# estop_tx.net
KiCad netlist of a schematic drawn in EAGLE
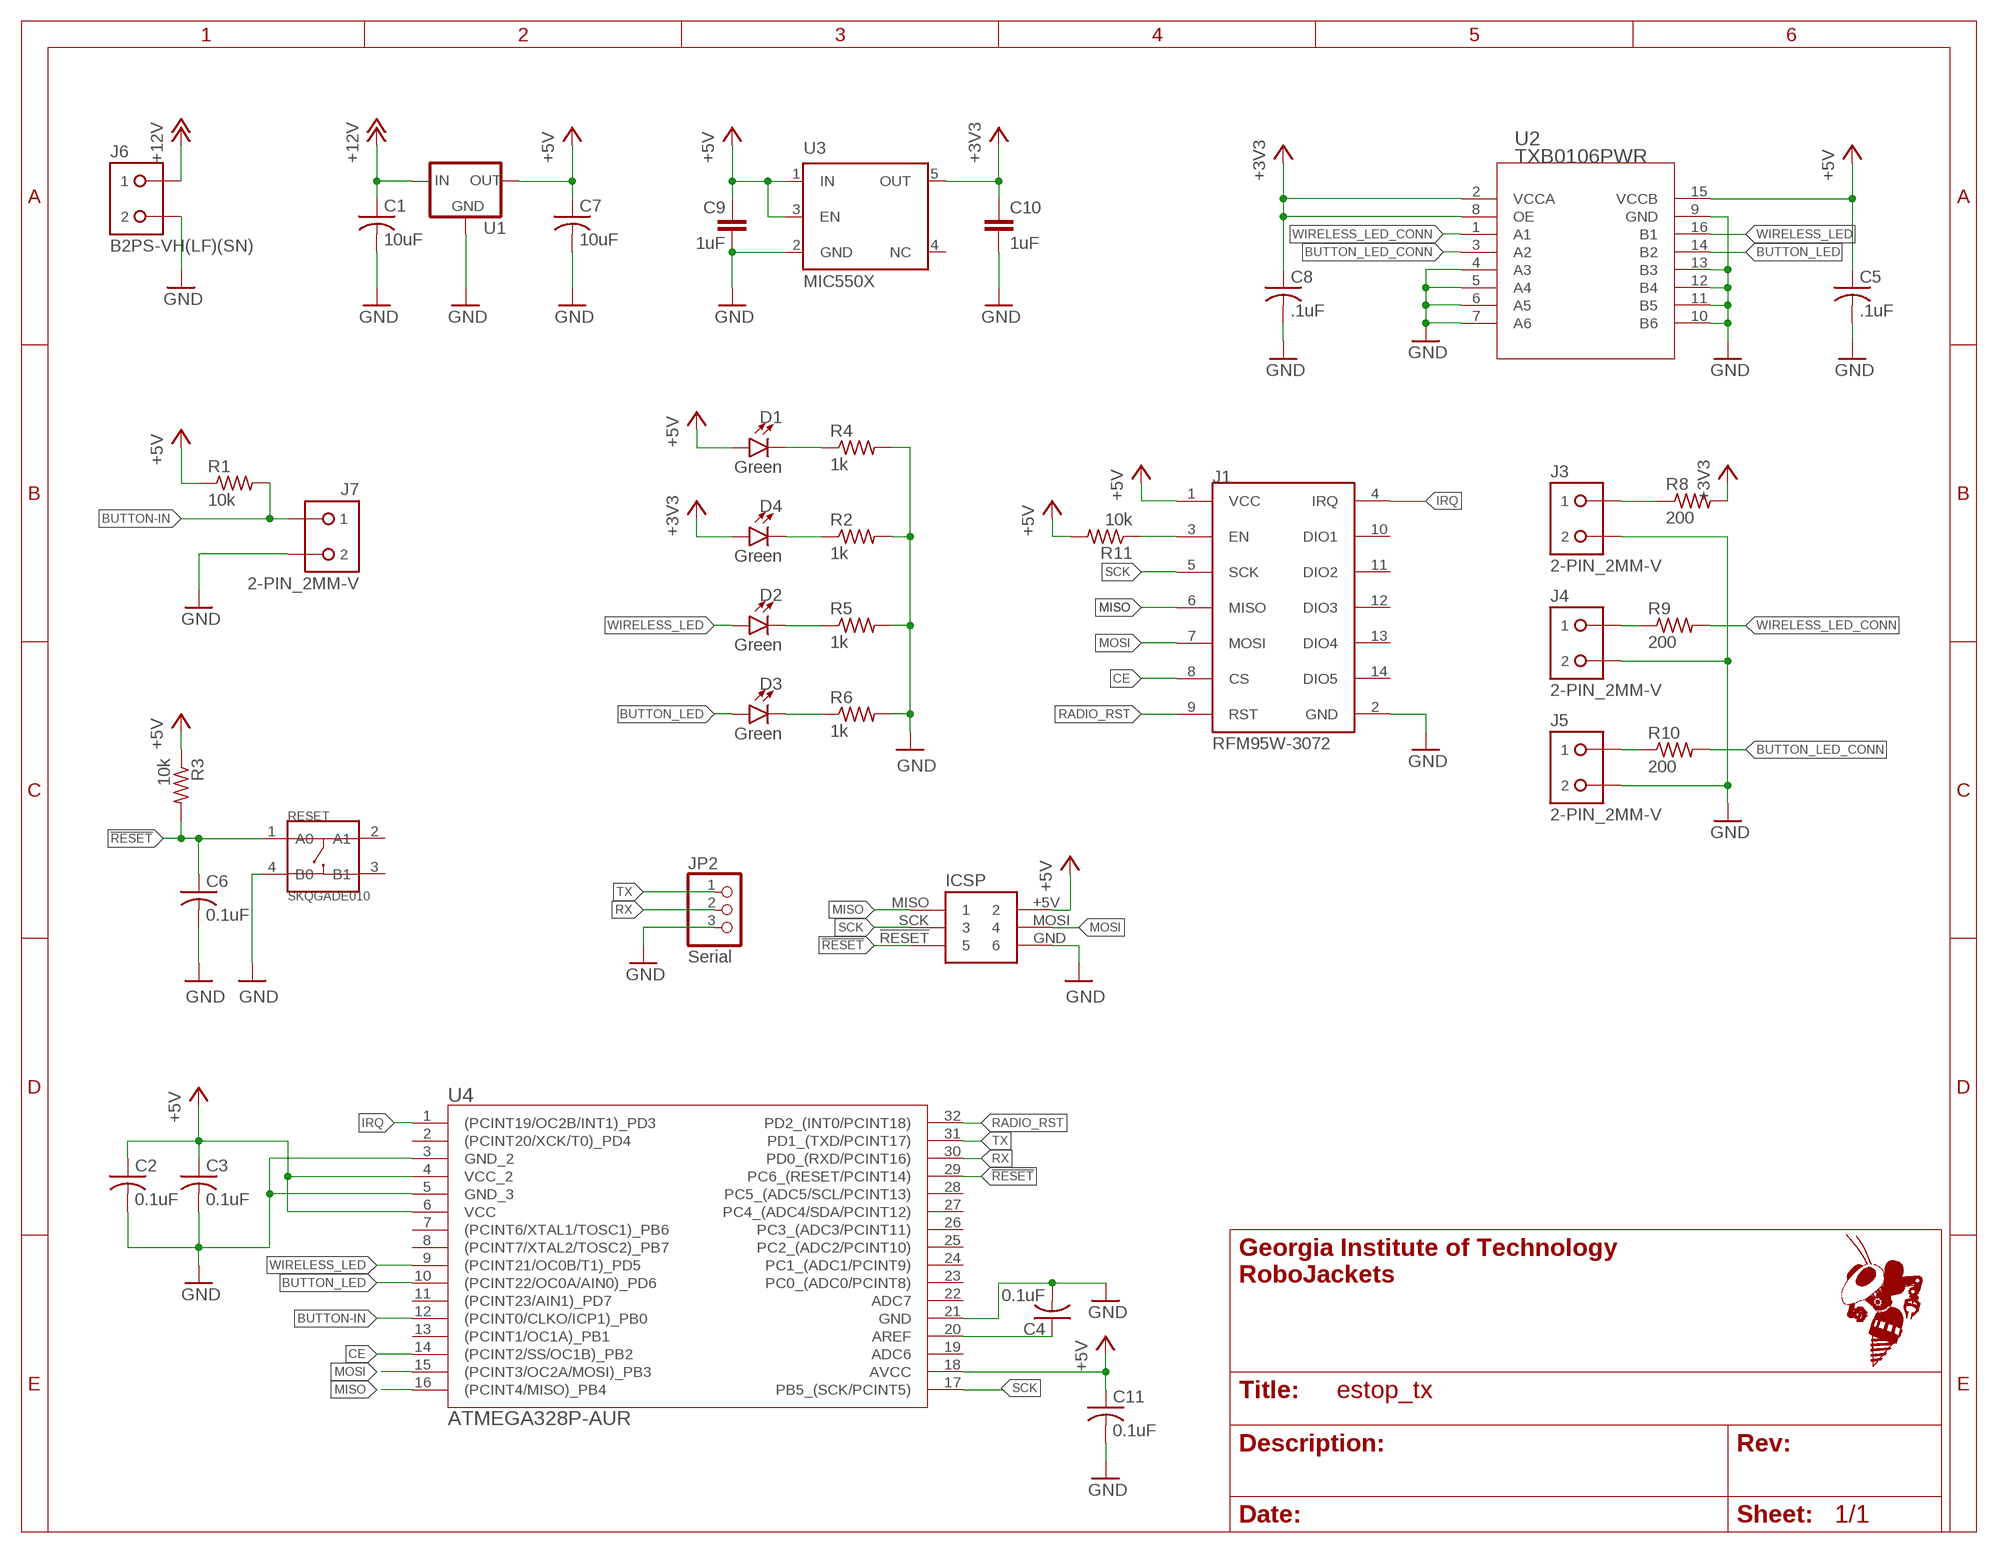
[diagram p0: schematic, sheet 1]

(export (version "E")
  (design (tool "Eeschema 10.0.6"))
  (components
    (comp (ref "C1")
      (value "10uF")
      (footprint "eagle-import:C0805")
      (libsource (lib "eagle-import") (part "C-USC0805"))
    )
    (comp (ref "C2")
      (value "0.1uF")
      (footprint "eagle-import:C0603")
      (libsource (lib "eagle-import") (part "C-USC0603"))
    )
    (comp (ref "C3")
      (value "0.1uF")
      (footprint "eagle-import:C0603")
      (libsource (lib "eagle-import") (part "C-USC0603"))
    )
    (comp (ref "C4")
      (value "0.1uF")
      (footprint "eagle-import:C0603")
      (libsource (lib "eagle-import") (part "C-USC0603"))
    )
    (comp (ref "C5")
      (value ".1uF")
      (footprint "eagle-import:C0603")
      (libsource (lib "eagle-import") (part "C-USC0603"))
    )
    (comp (ref "C6")
      (value "0.1uF")
      (footprint "eagle-import:C0603")
      (libsource (lib "eagle-import") (part "C-USC0603"))
    )
    (comp (ref "C7")
      (value "10uF")
      (footprint "eagle-import:C0805")
      (libsource (lib "eagle-import") (part "C-USC0805"))
    )
    (comp (ref "C8")
      (value ".1uF")
      (footprint "eagle-import:C0603")
      (libsource (lib "eagle-import") (part "C-USC0603"))
    )
    (comp (ref "C9")
      (value "1uF")
      (footprint "eagle-import:C0603")
      (libsource (lib "eagle-import") (part "C-EUC0603"))
    )
    (comp (ref "C10")
      (value "1uF")
      (footprint "eagle-import:C0603")
      (libsource (lib "eagle-import") (part "C-EUC0603"))
    )
    (comp (ref "C11")
      (value "0.1uF")
      (footprint "eagle-import:C0603")
      (libsource (lib "eagle-import") (part "C-USC0603"))
    )
    (comp (ref "D1")
      (value "Green")
      (footprint "eagle-import:LED-0603")
      (libsource (lib "eagle-import") (part "LED-YELLOW0603"))
    )
    (comp (ref "D2")
      (value "Green")
      (footprint "eagle-import:LED-0603")
      (libsource (lib "eagle-import") (part "LED-YELLOW0603"))
    )
    (comp (ref "D3")
      (value "Green")
      (footprint "eagle-import:LED-0603")
      (libsource (lib "eagle-import") (part "LED-YELLOW0603"))
    )
    (comp (ref "D4")
      (value "Green")
      (footprint "eagle-import:LED-0603")
      (libsource (lib "eagle-import") (part "LED-YELLOW0603"))
    )
    (comp (ref "ICSP")
      (value "ICSP Connector")
      (footprint "eagle-import:2X3SHROUDED")
      (libsource (lib "eagle-import") (part "2X3SHROUDED"))
    )
    (comp (ref "J1")
      (value "RFM95W-3072")
      (footprint "eagle-import:RFM95W-3072")
      (libsource (lib "eagle-import") (part "RFM95W-3072"))
    )
    (comp (ref "J3")
      (value "2-PIN_2MM-V")
      (footprint "eagle-import:2MM-2-V")
      (libsource (lib "eagle-import") (part "2-PIN_2MM-V"))
    )
    (comp (ref "J4")
      (value "2-PIN_2MM-V")
      (footprint "eagle-import:2MM-2-V")
      (libsource (lib "eagle-import") (part "2-PIN_2MM-V"))
    )
    (comp (ref "J5")
      (value "2-PIN_2MM-V")
      (footprint "eagle-import:2MM-2-V")
      (libsource (lib "eagle-import") (part "2-PIN_2MM-V"))
    )
    (comp (ref "J6")
      (value "B2PS-VH(LF)(SN)")
      (footprint "eagle-import:B2PS-CENTERED")
      (libsource (lib "eagle-import") (part "B2P?-VH(LF)(SN)S"))
    )
    (comp (ref "J7")
      (value "2-PIN_2MM-V")
      (footprint "eagle-import:2MM-2-V")
      (libsource (lib "eagle-import") (part "2-PIN_2MM-V"))
    )
    (comp (ref "JP2")
      (value "Serial")
      (footprint "eagle-import:1X03")
      (libsource (lib "eagle-import") (part "PINHD-1X3"))
    )
    (comp (ref "R1")
      (value "10k")
      (footprint "eagle-import:R0603")
      (libsource (lib "eagle-import") (part "resistor_348_R-US_R0603"))
    )
    (comp (ref "R2")
      (value "1k")
      (footprint "eagle-import:R0603")
      (libsource (lib "eagle-import") (part "R-US_R0603"))
    )
    (comp (ref "R3")
      (value "10k")
      (footprint "eagle-import:R0603")
      (libsource (lib "eagle-import") (part "R-US_R0603"))
    )
    (comp (ref "R4")
      (value "1k")
      (footprint "eagle-import:R0603")
      (libsource (lib "eagle-import") (part "R-US_R0603"))
    )
    (comp (ref "R5")
      (value "1k")
      (footprint "eagle-import:R0603")
      (libsource (lib "eagle-import") (part "R-US_R0603"))
    )
    (comp (ref "R6")
      (value "1k")
      (footprint "eagle-import:R0603")
      (libsource (lib "eagle-import") (part "R-US_R0603"))
    )
    (comp (ref "R8")
      (value "200")
      (footprint "eagle-import:R0603")
      (libsource (lib "eagle-import") (part "R-US_R0603"))
    )
    (comp (ref "R9")
      (value "200")
      (footprint "eagle-import:R0603")
      (libsource (lib "eagle-import") (part "R-US_R0603"))
    )
    (comp (ref "R10")
      (value "200")
      (footprint "eagle-import:R0603")
      (libsource (lib "eagle-import") (part "R-US_R0603"))
    )
    (comp (ref "R11")
      (value "10k")
      (footprint "eagle-import:R0603")
      (libsource (lib "eagle-import") (part "R-US_R0603"))
    )
    (comp (ref "RESET")
      (value "SKQGADE010")
      (footprint "eagle-import:SW4-SMD-5.2X5.2X1.5MM")
      (libsource (lib "eagle-import") (part "SMD-SWITCH-TOP-260GF(4P-D5.2MM)"))
    )
    (comp (ref "U1")
      (value "R-78E5.0-1.0CONV_R-78E5.0-1.0")
      (footprint "eagle-import:CONV_R-78E5.0-1.0")
      (libsource (lib "eagle-import") (part "R-78E5.0-1.0CONV_R-78E5.0-1.0"))
    )
    (comp (ref "U2")
      (value "TXB0106PWR")
      (footprint "eagle-import:PW16")
      (libsource (lib "eagle-import") (part "TXB0106PWR"))
    )
    (comp (ref "U3")
      (value "MIC550X")
      (footprint "eagle-import:SOT23-DBV")
      (libsource (lib "eagle-import") (part "MIC550X"))
    )
    (comp (ref "U4")
      (value "ATMEGA328P-AUR")
      (footprint "eagle-import:ATMEGA328P-AUR")
      (libsource (lib "eagle-import") (part "ATMEGA328P-AUR"))
    )
  )
  (nets
    (net (code "1") (name "+3V3") (class "Default")
      (node (ref "C10") (pin "1") (pinfunction "1_1") (pintype "passive"))
      (node (ref "C8") (pin "1") (pinfunction "1_1") (pintype "passive"))
      (node (ref "D4") (pin "A") (pinfunction "A_A") (pintype "passive"))
      (node (ref "R8") (pin "2") (pinfunction "2_2") (pintype "passive"))
      (node (ref "U2") (pin "2") (pinfunction "VCCA_2") (pintype "power_in"))
      (node (ref "U2") (pin "8") (pinfunction "OE_8") (pintype "output"))
      (node (ref "U3") (pin "5") (pinfunction "OUT_5") (pintype "passive"))
    )
    (net (code "2") (name "+5V") (class "Default")
      (node (ref "C11") (pin "1") (pinfunction "1_1") (pintype "passive"))
      (node (ref "C2") (pin "1") (pinfunction "1_1") (pintype "passive"))
      (node (ref "C3") (pin "1") (pinfunction "1_1") (pintype "passive"))
      (node (ref "C5") (pin "1") (pinfunction "1_1") (pintype "passive"))
      (node (ref "C7") (pin "1") (pinfunction "1_1") (pintype "passive"))
      (node (ref "C9") (pin "1") (pinfunction "1_1") (pintype "passive"))
      (node (ref "D1") (pin "A") (pinfunction "A_A") (pintype "passive"))
      (node (ref "ICSP") (pin "+5V") (pinfunction "2_+5V") (pintype "bidirectional"))
      (node (ref "J1") (pin "1") (pinfunction "VCC_1") (pintype "passive"))
      (node (ref "R1") (pin "1") (pinfunction "1_1") (pintype "passive"))
      (node (ref "R11") (pin "2") (pinfunction "2_2") (pintype "passive"))
      (node (ref "R3") (pin "1") (pinfunction "1_1") (pintype "passive"))
      (node (ref "U1") (pin "3") (pinfunction "OUT_3") (pintype "passive"))
      (node (ref "U2") (pin "15") (pinfunction "VCCB_15") (pintype "power_in"))
      (node (ref "U3") (pin "1") (pinfunction "IN_1") (pintype "input"))
      (node (ref "U3") (pin "3") (pinfunction "EN_3") (pintype "input"))
      (node (ref "U4") (pin "18") (pinfunction "AVCC_18") (pintype "bidirectional"))
      (node (ref "U4") (pin "4") (pinfunction "VCC_2_4") (pintype "bidirectional"))
      (node (ref "U4") (pin "6") (pinfunction "VCC_6") (pintype "bidirectional"))
    )
    (net (code "3") (name "+12V") (class "Default")
      (node (ref "C1") (pin "1") (pinfunction "1_1") (pintype "passive"))
      (node (ref "J6") (pin "1") (pinfunction "1_1") (pintype "bidirectional"))
      (node (ref "U1") (pin "1") (pinfunction "IN_1") (pintype "input"))
    )
    (net (code "4") (name "/~{RESET}") (class "Default")
      (node (ref "C6") (pin "1") (pinfunction "1_1") (pintype "passive"))
      (node (ref "ICSP") (pin "!RESET") (pinfunction "5_!RESET") (pintype "bidirectional"))
      (node (ref "R3") (pin "2") (pinfunction "2_2") (pintype "passive"))
      (node (ref "RESET") (pin "1") (pinfunction "A0_1") (pintype "bidirectional"))
      (node (ref "U4") (pin "29") (pinfunction "PC6_(RESET/PCINT14)_29") (pintype "bidirectional"))
    )
    (net (code "5") (name "BUTTON-IN") (class "Default")
      (node (ref "J7") (pin "1") (pinfunction "1_1") (pintype "bidirectional"))
      (node (ref "R1") (pin "2") (pinfunction "2_2") (pintype "passive"))
      (node (ref "U4") (pin "12") (pinfunction "(PCINT0/CLKO/ICP1)_PB0_12") (pintype "bidirectional"))
    )
    (net (code "6") (name "BUTTON_LED") (class "Default")
      (node (ref "D3") (pin "A") (pinfunction "A_A") (pintype "passive"))
      (node (ref "U2") (pin "14") (pinfunction "B2_14") (pintype "bidirectional"))
      (node (ref "U4") (pin "10") (pinfunction "(PCINT22/OC0A/AIN0)_PD6_10") (pintype "bidirectional"))
    )
    (net (code "7") (name "BUTTON_LED_CONN") (class "Default")
      (node (ref "R10") (pin "2") (pinfunction "2_2") (pintype "passive"))
      (node (ref "U2") (pin "3") (pinfunction "A2_3") (pintype "bidirectional"))
    )
    (net (code "8") (name "CE") (class "Default")
      (node (ref "J1") (pin "8") (pinfunction "CS_8") (pintype "passive"))
      (node (ref "U4") (pin "14") (pinfunction "(PCINT2/SS/OC1B)_PB2_14") (pintype "bidirectional"))
    )
    (net (code "9") (name "GND") (class "Default")
      (node (ref "C1") (pin "2") (pinfunction "2_2") (pintype "passive"))
      (node (ref "C10") (pin "2") (pinfunction "2_2") (pintype "passive"))
      (node (ref "C11") (pin "2") (pinfunction "2_2") (pintype "passive"))
      (node (ref "C2") (pin "2") (pinfunction "2_2") (pintype "passive"))
      (node (ref "C3") (pin "2") (pinfunction "2_2") (pintype "passive"))
      (node (ref "C4") (pin "2") (pinfunction "2_2") (pintype "passive"))
      (node (ref "C5") (pin "2") (pinfunction "2_2") (pintype "passive"))
      (node (ref "C6") (pin "2") (pinfunction "2_2") (pintype "passive"))
      (node (ref "C7") (pin "2") (pinfunction "2_2") (pintype "passive"))
      (node (ref "C8") (pin "2") (pinfunction "2_2") (pintype "passive"))
      (node (ref "C9") (pin "2") (pinfunction "2_2") (pintype "passive"))
      (node (ref "ICSP") (pin "GND") (pinfunction "6_GND") (pintype "bidirectional"))
      (node (ref "J1") (pin "2") (pinfunction "GND_2") (pintype "passive"))
      (node (ref "J3") (pin "2") (pinfunction "2_2") (pintype "bidirectional"))
      (node (ref "J4") (pin "2") (pinfunction "2_2") (pintype "bidirectional"))
      (node (ref "J5") (pin "2") (pinfunction "2_2") (pintype "bidirectional"))
      (node (ref "J6") (pin "2") (pinfunction "2_2") (pintype "bidirectional"))
      (node (ref "J7") (pin "2") (pinfunction "2_2") (pintype "bidirectional"))
      (node (ref "JP2") (pin "3") (pinfunction "3_3") (pintype "passive"))
      (node (ref "R2") (pin "2") (pinfunction "2_2") (pintype "passive"))
      (node (ref "R4") (pin "2") (pinfunction "2_2") (pintype "passive"))
      (node (ref "R5") (pin "2") (pinfunction "2_2") (pintype "passive"))
      (node (ref "R6") (pin "2") (pinfunction "2_2") (pintype "passive"))
      (node (ref "RESET") (pin "4") (pinfunction "B0_4") (pintype "bidirectional"))
      (node (ref "U1") (pin "2") (pinfunction "GND_2") (pintype "input"))
      (node (ref "U2") (pin "10") (pinfunction "B6_10") (pintype "bidirectional"))
      (node (ref "U2") (pin "11") (pinfunction "B5_11") (pintype "bidirectional"))
      (node (ref "U2") (pin "12") (pinfunction "B4_12") (pintype "bidirectional"))
      (node (ref "U2") (pin "13") (pinfunction "B3_13") (pintype "bidirectional"))
      (node (ref "U2") (pin "4") (pinfunction "A3_4") (pintype "bidirectional"))
      (node (ref "U2") (pin "5") (pinfunction "A4_5") (pintype "bidirectional"))
      (node (ref "U2") (pin "6") (pinfunction "A5_6") (pintype "bidirectional"))
      (node (ref "U2") (pin "7") (pinfunction "A6_7") (pintype "bidirectional"))
      (node (ref "U2") (pin "9") (pinfunction "GND_9") (pintype "power_in"))
      (node (ref "U3") (pin "2") (pinfunction "GND_2") (pintype "output"))
      (node (ref "U4") (pin "21") (pinfunction "GND_21") (pintype "bidirectional"))
      (node (ref "U4") (pin "3") (pinfunction "GND_2_3") (pintype "bidirectional"))
      (node (ref "U4") (pin "5") (pinfunction "GND_3_5") (pintype "bidirectional"))
    )
    (net (code "10") (name "IRQ") (class "Default")
      (node (ref "J1") (pin "4") (pinfunction "IRQ_4") (pintype "passive"))
      (node (ref "U4") (pin "1") (pinfunction "(PCINT19/OC2B/INT1)_PD3_1") (pintype "bidirectional"))
    )
    (net (code "11") (name "MISO") (class "Default")
      (node (ref "ICSP") (pin "MISO") (pinfunction "1_MISO") (pintype "bidirectional"))
      (node (ref "J1") (pin "6") (pinfunction "MISO_6") (pintype "passive"))
      (node (ref "U4") (pin "16") (pinfunction "(PCINT4/MISO)_PB4_16") (pintype "bidirectional"))
    )
    (net (code "12") (name "MOSI") (class "Default")
      (node (ref "ICSP") (pin "MOSI") (pinfunction "4_MOSI") (pintype "bidirectional"))
      (node (ref "J1") (pin "7") (pinfunction "MOSI_7") (pintype "passive"))
      (node (ref "U4") (pin "15") (pinfunction "(PCINT3/OC2A/MOSI)_PB3_15") (pintype "bidirectional"))
    )
    (net (code "13") (name "Net-(D1-PadC)") (class "Default")
      (node (ref "D1") (pin "C") (pinfunction "C_C") (pintype "passive"))
      (node (ref "R4") (pin "1") (pinfunction "1_1") (pintype "passive"))
    )
    (net (code "14") (name "Net-(D2-PadC)") (class "Default")
      (node (ref "D2") (pin "C") (pinfunction "C_C") (pintype "passive"))
      (node (ref "R5") (pin "1") (pinfunction "1_1") (pintype "passive"))
    )
    (net (code "15") (name "Net-(D3-PadC)") (class "Default")
      (node (ref "D3") (pin "C") (pinfunction "C_C") (pintype "passive"))
      (node (ref "R6") (pin "1") (pinfunction "1_1") (pintype "passive"))
    )
    (net (code "16") (name "Net-(D4-PadC)") (class "Default")
      (node (ref "D4") (pin "C") (pinfunction "C_C") (pintype "passive"))
      (node (ref "R2") (pin "1") (pinfunction "1_1") (pintype "passive"))
    )
    (net (code "17") (name "Net-(J1-EN)") (class "Default")
      (node (ref "J1") (pin "3") (pinfunction "EN_3") (pintype "passive"))
      (node (ref "R11") (pin "1") (pinfunction "1_1") (pintype "passive"))
    )
    (net (code "18") (name "Net-(J3-Pad1)") (class "Default")
      (node (ref "J3") (pin "1") (pinfunction "1_1") (pintype "bidirectional"))
      (node (ref "R8") (pin "1") (pinfunction "1_1") (pintype "passive"))
    )
    (net (code "19") (name "Net-(J4-Pad1)") (class "Default")
      (node (ref "J4") (pin "1") (pinfunction "1_1") (pintype "bidirectional"))
      (node (ref "R9") (pin "1") (pinfunction "1_1") (pintype "passive"))
    )
    (net (code "20") (name "Net-(J5-Pad1)") (class "Default")
      (node (ref "J5") (pin "1") (pinfunction "1_1") (pintype "bidirectional"))
      (node (ref "R10") (pin "1") (pinfunction "1_1") (pintype "passive"))
    )
    (net (code "21") (name "Net-(U4-AREF)") (class "Default")
      (node (ref "C4") (pin "1") (pinfunction "1_1") (pintype "passive"))
      (node (ref "U4") (pin "20") (pinfunction "AREF_20") (pintype "bidirectional"))
    )
    (net (code "22") (name "RADIO_RST") (class "Default")
      (node (ref "J1") (pin "9") (pinfunction "RST_9") (pintype "passive"))
      (node (ref "U4") (pin "32") (pinfunction "PD2_(INT0/PCINT18)_32") (pintype "bidirectional"))
    )
    (net (code "23") (name "RX") (class "Default")
      (node (ref "JP2") (pin "2") (pinfunction "2_2") (pintype "passive"))
      (node (ref "U4") (pin "30") (pinfunction "PD0_(RXD/PCINT16)_30") (pintype "bidirectional"))
    )
    (net (code "24") (name "SCK") (class "Default")
      (node (ref "ICSP") (pin "SCK") (pinfunction "3_SCK") (pintype "bidirectional"))
      (node (ref "J1") (pin "5") (pinfunction "SCK_5") (pintype "passive"))
      (node (ref "U4") (pin "17") (pinfunction "PB5_(SCK/PCINT5)_17") (pintype "bidirectional"))
    )
    (net (code "25") (name "TX") (class "Default")
      (node (ref "JP2") (pin "1") (pinfunction "1_1") (pintype "passive"))
      (node (ref "U4") (pin "31") (pinfunction "PD1_(TXD/PCINT17)_31") (pintype "bidirectional"))
    )
    (net (code "26") (name "WIRELESS_LED") (class "Default")
      (node (ref "D2") (pin "A") (pinfunction "A_A") (pintype "passive"))
      (node (ref "U2") (pin "16") (pinfunction "B1_16") (pintype "bidirectional"))
      (node (ref "U4") (pin "9") (pinfunction "(PCINT21/OC0B/T1)_PD5_9") (pintype "bidirectional"))
    )
    (net (code "27") (name "WIRELESS_LED_CONN") (class "Default")
      (node (ref "R9") (pin "2") (pinfunction "2_2") (pintype "passive"))
      (node (ref "U2") (pin "1") (pinfunction "A1_1") (pintype "bidirectional"))
    )
    (net (code "28") (name "unconnected-(J1-DIO1-Pad10)") (class "Default")
      (node (ref "J1") (pin "10") (pinfunction "DIO1_10") (pintype "bidirectional"))
    )
    (net (code "29") (name "unconnected-(J1-DIO2-Pad11)") (class "Default")
      (node (ref "J1") (pin "11") (pinfunction "DIO2_11") (pintype "bidirectional"))
    )
    (net (code "30") (name "unconnected-(J1-DIO3-Pad12)") (class "Default")
      (node (ref "J1") (pin "12") (pinfunction "DIO3_12") (pintype "bidirectional"))
    )
    (net (code "31") (name "unconnected-(J1-DIO4-Pad13)") (class "Default")
      (node (ref "J1") (pin "13") (pinfunction "DIO4_13") (pintype "bidirectional"))
    )
    (net (code "32") (name "unconnected-(J1-DIO5-Pad14)") (class "Default")
      (node (ref "J1") (pin "14") (pinfunction "DIO5_14") (pintype "bidirectional"))
    )
    (net (code "33") (name "unconnected-(RESET-A1-Pad2)") (class "Default")
      (node (ref "RESET") (pin "2") (pinfunction "A1_2") (pintype "bidirectional"))
    )
    (net (code "34") (name "unconnected-(RESET-B1-Pad3)") (class "Default")
      (node (ref "RESET") (pin "3") (pinfunction "B1_3") (pintype "bidirectional"))
    )
    (net (code "35") (name "unconnected-(U3-NC-Pad4)") (class "Default")
      (node (ref "U3") (pin "4") (pinfunction "NC_4") (pintype "tri_state"))
    )
    (net (code "36") (name "unconnected-(U4-(PCINT1{slash}OC1A)_PB1-Pad13)") (class "Default")
      (node (ref "U4") (pin "13") (pinfunction "(PCINT1/OC1A)_PB1_13") (pintype "bidirectional"))
    )
    (net (code "37") (name "unconnected-(U4-(PCINT6{slash}XTAL1{slash}TOSC1)_PB6-Pad7)") (class "Default")
      (node (ref "U4") (pin "7") (pinfunction "(PCINT6/XTAL1/TOSC1)_PB6_7") (pintype "bidirectional"))
    )
    (net (code "38") (name "unconnected-(U4-(PCINT7{slash}XTAL2{slash}TOSC2)_PB7-Pad8)") (class "Default")
      (node (ref "U4") (pin "8") (pinfunction "(PCINT7/XTAL2/TOSC2)_PB7_8") (pintype "bidirectional"))
    )
    (net (code "39") (name "unconnected-(U4-(PCINT20{slash}XCK{slash}T0)_PD4-Pad2)") (class "Default")
      (node (ref "U4") (pin "2") (pinfunction "(PCINT20/XCK/T0)_PD4_2") (pintype "bidirectional"))
    )
    (net (code "40") (name "unconnected-(U4-(PCINT23{slash}AIN1)_PD7-Pad11)") (class "Default")
      (node (ref "U4") (pin "11") (pinfunction "(PCINT23/AIN1)_PD7_11") (pintype "bidirectional"))
    )
    (net (code "41") (name "unconnected-(U4-ADC6-Pad19)") (class "Default")
      (node (ref "U4") (pin "19") (pinfunction "ADC6_19") (pintype "bidirectional"))
    )
    (net (code "42") (name "unconnected-(U4-ADC7-Pad22)") (class "Default")
      (node (ref "U4") (pin "22") (pinfunction "ADC7_22") (pintype "bidirectional"))
    )
    (net (code "43") (name "unconnected-(U4-PC0_(ADC0{slash}PCINT8)-Pad23)") (class "Default")
      (node (ref "U4") (pin "23") (pinfunction "PC0_(ADC0/PCINT8)_23") (pintype "bidirectional"))
    )
    (net (code "44") (name "unconnected-(U4-PC1_(ADC1{slash}PCINT9)-Pad24)") (class "Default")
      (node (ref "U4") (pin "24") (pinfunction "PC1_(ADC1/PCINT9)_24") (pintype "bidirectional"))
    )
    (net (code "45") (name "unconnected-(U4-PC2_(ADC2{slash}PCINT10)-Pad25)") (class "Default")
      (node (ref "U4") (pin "25") (pinfunction "PC2_(ADC2/PCINT10)_25") (pintype "bidirectional"))
    )
    (net (code "46") (name "unconnected-(U4-PC3_(ADC3{slash}PCINT11)-Pad26)") (class "Default")
      (node (ref "U4") (pin "26") (pinfunction "PC3_(ADC3/PCINT11)_26") (pintype "bidirectional"))
    )
    (net (code "47") (name "unconnected-(U4-PC4_(ADC4{slash}SDA{slash}PCINT12)-Pad27)") (class "Default")
      (node (ref "U4") (pin "27") (pinfunction "PC4_(ADC4/SDA/PCINT12)_27") (pintype "bidirectional"))
    )
    (net (code "48") (name "unconnected-(U4-PC5_(ADC5{slash}SCL{slash}PCINT13)-Pad28)") (class "Default")
      (node (ref "U4") (pin "28") (pinfunction "PC5_(ADC5/SCL/PCINT13)_28") (pintype "bidirectional"))
    )
  )
)
